# Rechargeable_Circuit.net
KiCad netlist of a schematic drawn in Altium Designer
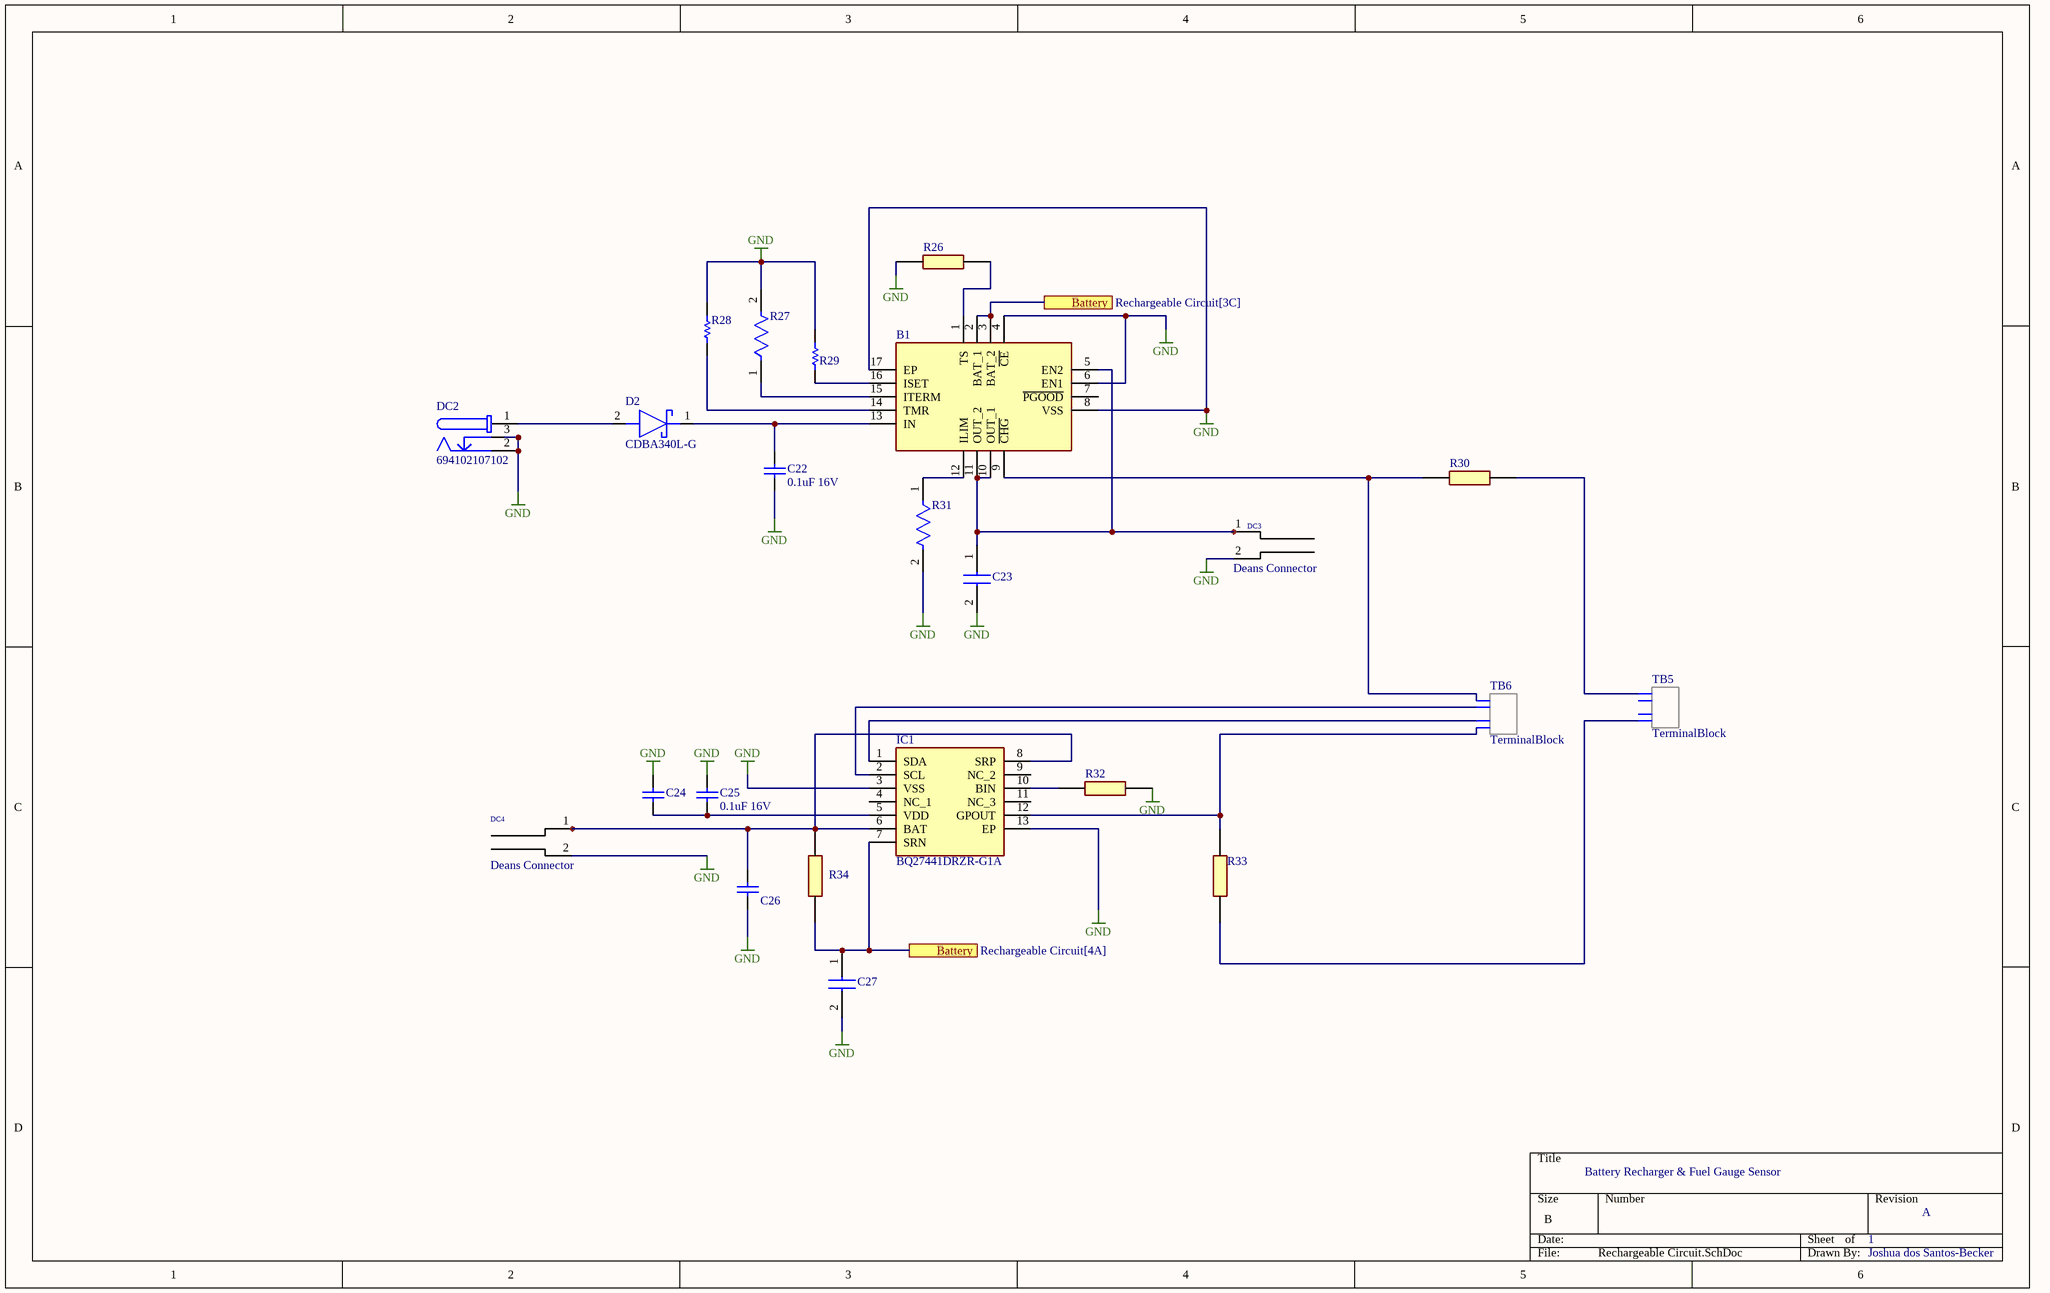
[diagram p0: Rechargeable Circuit.SchDoc]

(export (version "E")
  (design (tool "Eeschema 10.0.6"))
  (components
    (comp (ref "B1")
      (value "BQ24232HRGTR")
      (footprint "QFN50P300X300X100-17N-D")
      (description "USB-Friendly Lithium Based Battery Charger With Power-Path For 4.35V Batteries")
      (fields (field (name "MOUSER PART NUMBER") "595-BQ24232HRGTR"))
      (libsource (lib "gsl") (part "BQ24232HRGTR"))
    )
    (comp (ref "C22")
      (value "0.1uF 16V")
      (footprint "CAPC2113X100X50ML30T10")
      (description "C0805X104K4RACTU")
      (fields (field (name "MANUFACTURER") "Kemet"))
      (libsource (lib "Altium Content Vault") (part "CAP"))
    )
    (comp (ref "C23")
      (value "GRM32DR71C106KA01L")
      (footprint "gfl:GRM32DR61C106KA01L")
      (description "Capacitor")
      (fields (field (name "MOUSER PART NUMBER") "81-GRM32R71C106KA01L"))
      (libsource (lib "*") (part "GRM32DR71C106KA01L"))
    )
    (comp (ref "C24")
      (value "C1206C105K3RACTU")
      (footprint "CAPC3216X180X50ML20T25")
      (description "Chip Capacitor, 1 uF, +/- 10%, 25 V, -55 to 125 degC, 1206 (3216 Metric), RoHS, Tape and Reel")
      (fields (field (name "MANUFACTURER") "Kemet") (field (name "TOLERANCE") "10%"))
      (libsource (lib "Altium Content Vault") (part "CAP-NP-2"))
    )
    (comp (ref "C25")
      (value "0.1uF 16V")
      (footprint "CAPC2113X100X50ML30T10")
      (description "C0805X104K4RACTU")
      (fields (field (name "MANUFACTURER") "Kemet"))
      (libsource (lib "Altium Content Vault") (part "CAP"))
    )
    (comp (ref "C26")
      (value "C1206C105K3RACTU")
      (footprint "CAPC3216X180X50ML20T25")
      (description "Chip Capacitor, 1 uF, +/- 10%, 25 V, -55 to 125 degC, 1206 (3216 Metric), RoHS, Tape and Reel")
      (fields (field (name "MANUFACTURER") "Kemet") (field (name "TOLERANCE") "10%"))
      (libsource (lib "Altium Content Vault") (part "CAP-NP-2"))
    )
    (comp (ref "C27")
      (value "GRM32DR71C106KA01L")
      (footprint "gfl:GRM32DR61C106KA01L")
      (description "Capacitor")
      (fields (field (name "MOUSER PART NUMBER") "81-GRM32R71C106KA01L"))
      (libsource (lib "*") (part "GRM32DR71C106KA01L"))
    )
    (comp (ref "D2")
      (value "CDBA340L-G")
      (footprint "DIONM5127X229N")
      (description "Schottky Diode")
      (fields (field (name "MOUSER PART NUMBER") "750-CDBA340L-G"))
      (libsource (lib "gsl") (part "CDBA340L-G"))
    )
    (comp (ref "DC2")
      (value "694102107102")
      (footprint "694102107102")
      (libsource (lib "gsl") (part "DC Power Jack"))
    )
    (comp (ref "DC3")
      (value "Deans Connector")
      (footprint "Deans")
      (libsource (lib "gsl") (part "Deans Connector"))
    )
    (comp (ref "DC4")
      (value "Deans Connector")
      (footprint "Deans")
      (libsource (lib "gsl") (part "Deans Connector"))
    )
    (comp (ref "IC1")
      (value "BQ27441DRZR-G1A")
      (footprint "gfl:BQ27441DRZRG1A")
      (description "Integrated Circuit")
      (fields (field (name "MOUSER PART NUMBER") "595-BQ27441DRZR-G1A"))
      (libsource (lib "gsl") (part "BQ27441DRZR-G1A"))
    )
    (comp (ref "R26")
      (value "CRM2512QJW-103ELF")
      (footprint "RESC6331X80N")
      (description "ResPowerQ 2512 10k 5% 2W TC200")
      (fields (field (name "MOUSER PART NUMBER") "652-CRM2512QJW-103E"))
      (libsource (lib "gsl") (part "CRM2512QJW-103ELF"))
    )
    (comp (ref "R27")
      (value "RG2012V-1431-B-T5")
      (footprint "FP-RG2012-MFG")
      (description "Automotive Metal Thin Film Chip Resistor, 0805, 1.43kΩ, 0.1%, 5ppm/°C, 0.125W, 150V")
      (fields (field (name "TOLERANCE") "0.1%"))
      (libsource (lib "Altium Content Vault") (part "1029c3af85768c4190bb7ad29bc67b5"))
    )
    (comp (ref "R28")
      (value "CRCW120656K2FKEA")
      (footprint "RESC3216X60X45ML10T20")
      (fields (field (name "MANUFACTURER") "Vishay Dale"))
      (libsource (lib "Altium Content Vault") (part "RES"))
    )
    (comp (ref "R29")
      (value "1K74 1% 2010(5025)")
      (footprint "RESC2010(5025)_L")
      (description "1K74 0.75W 1% 2010 (5025 Metric)  SMD")
      (fields (field (name "POWER") "0.75 W") (field (name "TOLERANCE") "1 %"))
      (libsource (lib "Altium Content Vault") (part "RES"))
    )
    (comp (ref "R30")
      (value "CRM2512QJW-103ELF")
      (footprint "RESC6331X80N")
      (description "ResPowerQ 2512 10k 5% 2W TC200")
      (fields (field (name "MOUSER PART NUMBER") "652-CRM2512QJW-103E"))
      (libsource (lib "gsl") (part "CRM2512QJW-103ELF"))
    )
    (comp (ref "R31")
      (value "CRCW08053K09FKEA")
      (footprint "FP-CRCW0805-e3-IPC_C")
      (description "RES Thick Film, 3.09kΩ, 1%, 0.125W, 100ppm/°C, 0805")
      (fields (field (name "TOLERANCE") "1%"))
      (libsource (lib "Altium Content Vault") (part "1029c3af85768c4190bb7ad29bc67b5"))
    )
    (comp (ref "R32")
      (value "CRM2512QJW-103ELF")
      (footprint "RESC6331X80N")
      (description "ResPowerQ 2512 10k 5% 2W TC200")
      (fields (field (name "MOUSER PART NUMBER") "652-CRM2512QJW-103E"))
      (libsource (lib "gsl") (part "CRM2512QJW-103ELF"))
    )
    (comp (ref "R33")
      (value "CRM2512QJW-103ELF")
      (footprint "RESC6331X80N")
      (description "ResPowerQ 2512 10k 5% 2W TC200")
      (fields (field (name "MOUSER PART NUMBER") "652-CRM2512QJW-103E"))
      (libsource (lib "") (part "CRM2512QJW-103ELF_1"))
    )
    (comp (ref "R34")
      (value "CRM2512QJW-103ELF")
      (footprint "RESC6331X80N")
      (description "ResPowerQ 2512 10k 5% 2W TC200")
      (fields (field (name "MOUSER PART NUMBER") "652-CRM2512QJW-103E"))
      (libsource (lib "") (part "CRM2512QJW-103ELF_2"))
    )
    (comp (ref "TB5")
      (value "TerminalBlock")
      (footprint "PHOENIX_1725672")
      (libsource (lib "gsl") (part "TerminalBlock"))
    )
    (comp (ref "TB6")
      (value "TerminalBlock")
      (footprint "PHOENIX_1725672")
      (libsource (lib "gsl") (part "TerminalBlock"))
    )
  )
  (nets
    (net (code "1") (name "/Battery") (class "Default")
      (node (ref "B1") (pin "2") (pinfunction "BAT_1_2") (pintype "passive"))
      (node (ref "B1") (pin "3") (pinfunction "BAT_2_3") (pintype "passive"))
      (node (ref "C27") (pin "1") (pinfunction "1_1") (pintype "passive"))
      (node (ref "IC1") (pin "7") (pinfunction "SRN_7") (pintype "passive"))
      (node (ref "R34") (pin "1") (pinfunction "1_1") (pintype "passive"))
    )
    (net (code "2") (name "GND") (class "Default")
      (node (ref "B1") (pin "17") (pinfunction "EP_17") (pintype "passive"))
      (node (ref "B1") (pin "4") (pinfunction "~{CE}_4") (pintype "passive"))
      (node (ref "B1") (pin "6") (pinfunction "EN1_6") (pintype "passive"))
      (node (ref "B1") (pin "8") (pinfunction "VSS_8") (pintype "passive"))
      (node (ref "C22") (pin "2") (pinfunction "2_2") (pintype "passive"))
      (node (ref "C23") (pin "2") (pinfunction "2_2") (pintype "passive"))
      (node (ref "C24") (pin "1") (pinfunction "1_1") (pintype "passive"))
      (node (ref "C25") (pin "1") (pinfunction "1_1") (pintype "passive"))
      (node (ref "C26") (pin "1") (pinfunction "1_1") (pintype "passive"))
      (node (ref "C27") (pin "2") (pinfunction "2_2") (pintype "passive"))
      (node (ref "DC2") (pin "2") (pinfunction "2_2") (pintype "passive"))
      (node (ref "DC2") (pin "3") (pinfunction "3_3") (pintype "passive"))
      (node (ref "DC3") (pin "2") (pinfunction "2_2") (pintype "passive"))
      (node (ref "DC4") (pin "2") (pinfunction "2_2") (pintype "passive"))
      (node (ref "IC1") (pin "13") (pinfunction "EP_13") (pintype "passive"))
      (node (ref "IC1") (pin "3") (pinfunction "VSS_3") (pintype "passive"))
      (node (ref "R26") (pin "1") (pinfunction "1_1") (pintype "passive"))
      (node (ref "R27") (pin "2") (pinfunction "2_2") (pintype "passive"))
      (node (ref "R28") (pin "1") (pinfunction "1_1") (pintype "passive"))
      (node (ref "R29") (pin "2") (pinfunction "2_2") (pintype "passive"))
      (node (ref "R31") (pin "2") (pinfunction "2_2") (pintype "passive"))
      (node (ref "R32") (pin "2") (pinfunction "2_2") (pintype "passive"))
    )
    (net (code "3") (name "Net-(B1-EN2)") (class "Default")
      (node (ref "B1") (pin "10") (pinfunction "OUT_1_10") (pintype "passive"))
      (node (ref "B1") (pin "11") (pinfunction "OUT_2_11") (pintype "passive"))
      (node (ref "B1") (pin "5") (pinfunction "EN2_5") (pintype "passive"))
      (node (ref "C23") (pin "1") (pinfunction "1_1") (pintype "passive"))
      (node (ref "DC3") (pin "1") (pinfunction "1_1") (pintype "passive"))
    )
    (net (code "4") (name "Net-(B1-ILIM)") (class "Default")
      (node (ref "B1") (pin "12") (pinfunction "ILIM_12") (pintype "passive"))
      (node (ref "R31") (pin "1") (pinfunction "1_1") (pintype "passive"))
    )
    (net (code "5") (name "Net-(B1-IN)") (class "Default")
      (node (ref "B1") (pin "13") (pinfunction "IN_13") (pintype "passive"))
      (node (ref "C22") (pin "1") (pinfunction "1_1") (pintype "passive"))
      (node (ref "D2") (pin "1") (pinfunction "K_1") (pintype "passive"))
    )
    (net (code "6") (name "Net-(B1-ISET)") (class "Default")
      (node (ref "B1") (pin "16") (pinfunction "ISET_16") (pintype "passive"))
      (node (ref "R29") (pin "1") (pinfunction "1_1") (pintype "passive"))
    )
    (net (code "7") (name "Net-(B1-ITERM)") (class "Default")
      (node (ref "B1") (pin "15") (pinfunction "ITERM_15") (pintype "passive"))
      (node (ref "R27") (pin "1") (pinfunction "1_1") (pintype "passive"))
    )
    (net (code "8") (name "Net-(B1-TMR)") (class "Default")
      (node (ref "B1") (pin "14") (pinfunction "TMR_14") (pintype "passive"))
      (node (ref "R28") (pin "2") (pinfunction "2_2") (pintype "passive"))
    )
    (net (code "9") (name "Net-(B1-TS)") (class "Default")
      (node (ref "B1") (pin "1") (pinfunction "TS_1") (pintype "passive"))
      (node (ref "R26") (pin "2") (pinfunction "2_2") (pintype "passive"))
    )
    (net (code "10") (name "Net-(B1-~{CHG})") (class "Default")
      (node (ref "B1") (pin "9") (pinfunction "~{CHG}_9") (pintype "passive"))
      (node (ref "R30") (pin "1") (pinfunction "1_1") (pintype "passive"))
      (node (ref "TB6") (pin "1") (pinfunction "1_1") (pintype "passive"))
    )
    (net (code "11") (name "Net-(D2-A)") (class "Default")
      (node (ref "D2") (pin "2") (pinfunction "A_2") (pintype "passive"))
      (node (ref "DC2") (pin "1") (pinfunction "1_1") (pintype "passive"))
    )
    (net (code "12") (name "Net-(IC1-BAT)") (class "Default")
      (node (ref "C26") (pin "2") (pinfunction "2_2") (pintype "passive"))
      (node (ref "DC4") (pin "1") (pinfunction "1_1") (pintype "passive"))
      (node (ref "IC1") (pin "6") (pinfunction "BAT_6") (pintype "passive"))
      (node (ref "IC1") (pin "8") (pinfunction "SRP_8") (pintype "passive"))
      (node (ref "R34") (pin "2") (pinfunction "2_2") (pintype "passive"))
    )
    (net (code "13") (name "Net-(IC1-BIN)") (class "Default")
      (node (ref "IC1") (pin "10") (pinfunction "BIN_10") (pintype "passive"))
      (node (ref "R32") (pin "1") (pinfunction "1_1") (pintype "passive"))
    )
    (net (code "14") (name "Net-(IC1-GPOUT)") (class "Default")
      (node (ref "IC1") (pin "12") (pinfunction "GPOUT_12") (pintype "passive"))
      (node (ref "R33") (pin "1") (pinfunction "1_1") (pintype "passive"))
      (node (ref "TB6") (pin "4") (pinfunction "4_4") (pintype "passive"))
    )
    (net (code "15") (name "Net-(IC1-SCL)") (class "Default")
      (node (ref "IC1") (pin "2") (pinfunction "SCL_2") (pintype "passive"))
      (node (ref "TB6") (pin "2") (pinfunction "2_2") (pintype "passive"))
    )
    (net (code "16") (name "Net-(IC1-SDA)") (class "Default")
      (node (ref "IC1") (pin "1") (pinfunction "SDA_1") (pintype "passive"))
      (node (ref "TB6") (pin "3") (pinfunction "3_3") (pintype "passive"))
    )
    (net (code "17") (name "Net-(IC1-VDD)") (class "Default")
      (node (ref "C24") (pin "2") (pinfunction "2_2") (pintype "passive"))
      (node (ref "C25") (pin "2") (pinfunction "2_2") (pintype "passive"))
      (node (ref "IC1") (pin "5") (pinfunction "VDD_5") (pintype "passive"))
    )
    (net (code "18") (name "Net-(R30-Pad2)") (class "Default")
      (node (ref "R30") (pin "2") (pinfunction "2_2") (pintype "passive"))
      (node (ref "TB5") (pin "1") (pinfunction "1_1") (pintype "passive"))
    )
    (net (code "19") (name "Net-(R33-Pad2)") (class "Default")
      (node (ref "R33") (pin "2") (pinfunction "2_2") (pintype "passive"))
      (node (ref "TB5") (pin "4") (pinfunction "4_4") (pintype "passive"))
    )
    (net (code "20") (name "unconnected-(B1-~{PGOOD}-Pad7)") (class "Default")
      (node (ref "B1") (pin "7") (pinfunction "~{PGOOD}_7") (pintype "passive"))
    )
    (net (code "21") (name "unconnected-(IC1-NC_1-Pad4)") (class "Default")
      (node (ref "IC1") (pin "4") (pinfunction "NC_1_4") (pintype "passive"))
    )
    (net (code "22") (name "unconnected-(IC1-NC_2-Pad9)") (class "Default")
      (node (ref "IC1") (pin "9") (pinfunction "NC_2_9") (pintype "passive"))
    )
    (net (code "23") (name "unconnected-(IC1-NC_3-Pad11)") (class "Default")
      (node (ref "IC1") (pin "11") (pinfunction "NC_3_11") (pintype "passive"))
    )
    (net (code "24") (name "unconnected-(TB5-Pad2)") (class "Default")
      (node (ref "TB5") (pin "2") (pinfunction "2_2") (pintype "passive"))
    )
    (net (code "25") (name "unconnected-(TB5-Pad3)") (class "Default")
      (node (ref "TB5") (pin "3") (pinfunction "3_3") (pintype "passive"))
    )
  )
)
